# isolator.net
KiCad netlist of a schematic drawn in Altium Designer
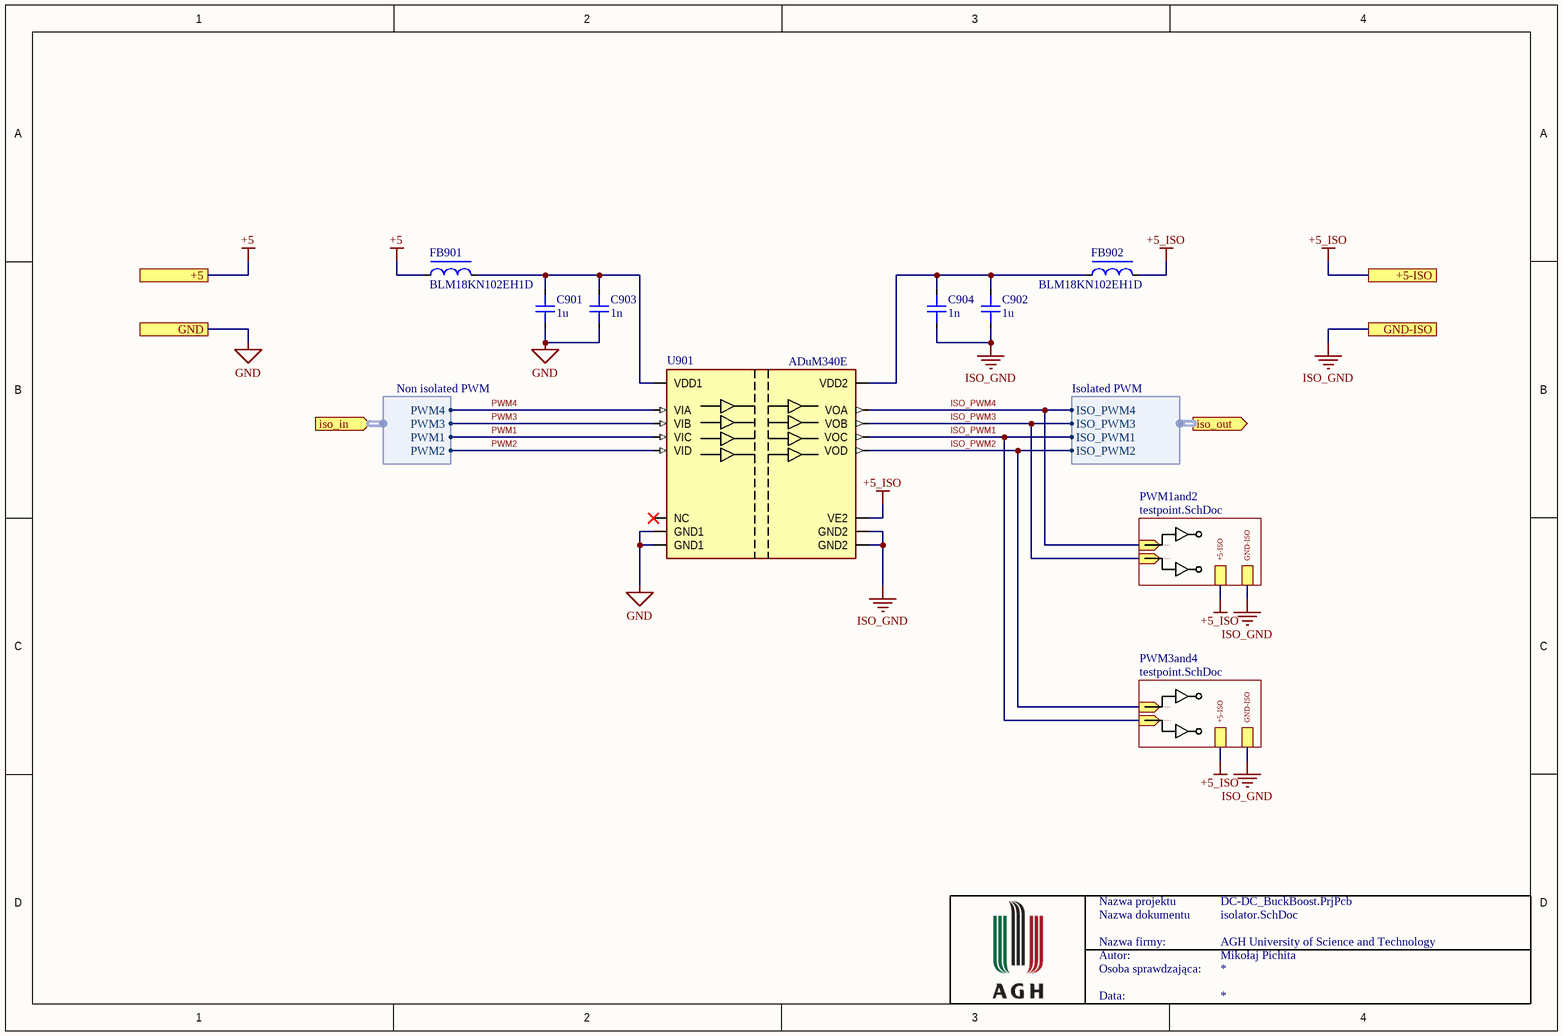
[diagram p0: isolator.SchDoc]

(export (version "E")
  (design (tool "Eeschema 10.0.6"))
  (components
    (comp (ref "C901")
      (value "1u")
      (footprint "CAP0603")
      (libsource (lib "schematic_library") (part "Capacitor"))
    )
    (comp (ref "C902")
      (value "1u")
      (footprint "CAP0603")
      (libsource (lib "schematic_library") (part "Capacitor"))
    )
    (comp (ref "C903")
      (value "1n")
      (footprint "CAP0603")
      (libsource (lib "schematic_library") (part "Capacitor"))
    )
    (comp (ref "C904")
      (value "1n")
      (footprint "CAP0603")
      (libsource (lib "schematic_library") (part "Capacitor"))
    )
    (comp (ref "FB901")
      (value "BLM18KN102EH1D")
      (footprint "RES0603")
      (libsource (lib "schematic_library") (part "Ferrite Bead"))
    )
    (comp (ref "FB902")
      (value "BLM18KN102EH1D")
      (footprint "RES0603")
      (libsource (lib "schematic_library") (part "Ferrite Bead"))
    )
    (comp (ref "U901")
      (value "ADuM340E")
      (footprint "SOIC127P1030X265-16N")
      (description "5.7 kV rms Quad Digital Isolators")
      (libsource (lib "schematic_library") (part "ADuM340E"))
    )
  )
  (nets
    (net (code "5") (name "+5") (class "Default") (node (ref "FB901") (pin "2") (pintype "passive")))
    (net (code "6") (name "+5_ISO") (class "Default")
      (node (ref "FB902") (pin "1") (pintype "passive"))
      (node (ref "U901") (pin "10") (pinfunction "VE2_10") (pintype "passive"))
    )
    (net (code "7") (name "/ISO_PWM1") (class "Default")
      (node (ref "U901") (pin "12") (pinfunction "VOC_12") (pintype "output"))
    )
    (net (code "8") (name "/ISO_PWM2") (class "Default")
      (node (ref "U901") (pin "11") (pinfunction "VOD_11") (pintype "output"))
    )
    (net (code "9") (name "/ISO_PWM3") (class "Default")
      (node (ref "U901") (pin "13") (pinfunction "VOB_13") (pintype "output"))
    )
    (net (code "10") (name "/ISO_PWM4") (class "Default")
      (node (ref "U901") (pin "14") (pinfunction "VOA_14") (pintype "output"))
    )
    (net (code "11") (name "/PWM1") (class "Default")
      (node (ref "U901") (pin "5") (pinfunction "VIC_5") (pintype "input"))
    )
    (net (code "12") (name "/PWM2") (class "Default")
      (node (ref "U901") (pin "6") (pinfunction "VID_6") (pintype "input"))
    )
    (net (code "13") (name "/PWM3") (class "Default")
      (node (ref "U901") (pin "4") (pinfunction "VIB_4") (pintype "input"))
    )
    (net (code "14") (name "/PWM4") (class "Default")
      (node (ref "U901") (pin "3") (pinfunction "VIA_3") (pintype "input"))
    )
    (net (code "17") (name "GND") (class "Default")
      (node (ref "C901") (pin "1") (pintype "passive"))
      (node (ref "C903") (pin "2") (pintype "passive"))
      (node (ref "U901") (pin "2") (pinfunction "GND1_2") (pintype "power_in"))
      (node (ref "U901") (pin "8") (pinfunction "GND1_8") (pintype "power_in"))
    )
    (net (code "18") (name "ISO_GND") (class "Default")
      (node (ref "C902") (pin "1") (pintype "passive"))
      (node (ref "C904") (pin "2") (pintype "passive"))
      (node (ref "U901") (pin "15") (pinfunction "GND2_15") (pintype "power_in"))
      (node (ref "U901") (pin "9") (pinfunction "GND2_9") (pintype "power_in"))
    )
    (net (code "19") (name "Net-(U901-VDD1)") (class "Default")
      (node (ref "C901") (pin "2") (pintype "passive"))
      (node (ref "C903") (pin "1") (pintype "passive"))
      (node (ref "FB901") (pin "1") (pintype "passive"))
      (node (ref "U901") (pin "1") (pinfunction "VDD1_1") (pintype "power_in"))
    )
    (net (code "20") (name "Net-(U901-VDD2)") (class "Default")
      (node (ref "C902") (pin "2") (pintype "passive"))
      (node (ref "C904") (pin "1") (pintype "passive"))
      (node (ref "FB902") (pin "2") (pintype "passive"))
      (node (ref "U901") (pin "16") (pinfunction "VDD2_16") (pintype "power_in"))
    )
    (net (code "21") (name "unconnected-(U901-NC-Pad7)") (class "Default")
      (node (ref "U901") (pin "7") (pinfunction "NC_7") (pintype "passive+no_connect"))
    )
  )
)
